# 2S_BATTERY_CHARGER_SCH.net
KiCad netlist of a schematic drawn in Altium Designer
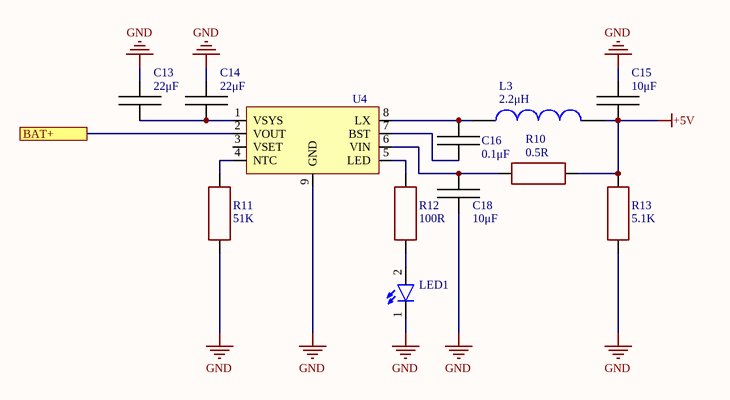
[diagram p0: 2S_BATTERY_CHARGER_SCH.SchDoc]

(export (version "E")
  (design (tool "Eeschema 10.0.6"))
  (components
    (comp (ref "C13")
      (value "22μF")
      (footprint "CAP: 0603")
      (fields (field (name "VOLTAGE") "??V") (field (name "Comment") "Cap_0603"))
      (libsource (lib "capacitor") (part "Cap_0603"))
    )
    (comp (ref "C14")
      (value "22μF")
      (footprint "CAP: 0603")
      (fields (field (name "VOLTAGE") "??V") (field (name "Comment") "Cap_0603"))
      (libsource (lib "capacitor") (part "Cap_0603"))
    )
    (comp (ref "C15")
      (value "10μF")
      (footprint "CAP: 0603")
      (fields (field (name "VOLTAGE") "??V") (field (name "Comment") "Cap_0603"))
      (libsource (lib "capacitor") (part "Cap_0603"))
    )
    (comp (ref "C16")
      (value "0.1μF")
      (footprint "CAP: 0603")
      (fields (field (name "VOLTAGE") "??V") (field (name "Comment") "Cap_0603"))
      (libsource (lib "capacitor") (part "Cap_0603"))
    )
    (comp (ref "C18")
      (value "10μF")
      (footprint "CAP: 0603")
      (fields (field (name "VOLTAGE") "??V") (field (name "Comment") "Cap_0603"))
      (libsource (lib "capacitor") (part "Cap_0603"))
    )
    (comp (ref "L3")
      (value "2.2μH")
      (footprint "CD43")
      (description "SMD Power Inductor")
      (fields (field (name "MANUFACTURER") "SUMIDA") (field (name "Comment") "CD43"))
      (libsource (lib "MY_INT_LIB") (part "CD43"))
    )
    (comp (ref "LED1")
      (value "LED_0603")
      (footprint "LED_0603")
      (libsource (lib "MY_INT_LIB") (part "LED_0603"))
    )
    (comp (ref "R10")
      (value "0.5R")
      (footprint "RES: 0603")
      (fields (field (name "TOLERANCE") "±5%") (field (name "Comment") "Resistor_0603"))
      (libsource (lib "") (part "Resistor_0603_1"))
    )
    (comp (ref "R11")
      (value "51K")
      (footprint "RES: 0603")
      (fields (field (name "TOLERANCE") "±5%") (field (name "Comment") "Resistor_0603"))
      (libsource (lib "resistor") (part "Resistor_0603"))
    )
    (comp (ref "R12")
      (value "100R")
      (footprint "RES: 0603")
      (fields (field (name "TOLERANCE") "±5%") (field (name "Comment") "Resistor_0603"))
      (libsource (lib "resistor") (part "Resistor_0603"))
    )
    (comp (ref "R13")
      (value "5.1K")
      (footprint "RES: 0603")
      (fields (field (name "TOLERANCE") "±5%") (field (name "Comment") "Resistor_0603"))
      (libsource (lib "resistor") (part "Resistor_0603"))
    )
    (comp (ref "U4")
      (value "IP2325")
      (footprint "ESOP-8")
      (description "2s charge Module")
      (fields (field (name "MANUFACTURER") "INJOINIC"))
      (libsource (lib "MY_INT_LIB") (part "IP2325"))
    )
  )
  (nets
    (net (code "1") (name "+5V") (class "Default")
      (node (ref "C15") (pin "2") (pinfunction "2_2") (pintype "passive"))
      (node (ref "L3") (pin "1") (pinfunction "1_1") (pintype "passive"))
      (node (ref "R10") (pin "1") (pinfunction "1_1") (pintype "passive"))
      (node (ref "R13") (pin "2") (pinfunction "2_2") (pintype "passive"))
    )
    (net (code "2") (name "/BAT+") (class "Default")
      (node (ref "U4") (pin "2") (pinfunction "VOUT_2") (pintype "passive"))
    )
    (net (code "3") (name "GND") (class "Default")
      (node (ref "C13") (pin "1") (pinfunction "1_1") (pintype "passive"))
      (node (ref "C14") (pin "1") (pinfunction "1_1") (pintype "passive"))
      (node (ref "C15") (pin "1") (pinfunction "1_1") (pintype "passive"))
      (node (ref "C18") (pin "1") (pinfunction "1_1") (pintype "passive"))
      (node (ref "LED1") (pin "1") (pintype "passive"))
      (node (ref "R11") (pin "1") (pinfunction "1_1") (pintype "passive"))
      (node (ref "R13") (pin "1") (pinfunction "1_1") (pintype "passive"))
      (node (ref "U4") (pin "9") (pinfunction "GND_9") (pintype "passive"))
    )
    (net (code "4") (name "Net-(LED1-Pad2)") (class "Default")
      (node (ref "LED1") (pin "2") (pintype "passive"))
      (node (ref "R12") (pin "1") (pinfunction "1_1") (pintype "passive"))
    )
    (net (code "5") (name "Net-(U4-BST)") (class "Default")
      (node (ref "C16") (pin "1") (pinfunction "1_1") (pintype "passive"))
      (node (ref "U4") (pin "7") (pinfunction "BST_7") (pintype "passive"))
    )
    (net (code "6") (name "Net-(U4-LED)") (class "Default")
      (node (ref "R12") (pin "2") (pinfunction "2_2") (pintype "passive"))
      (node (ref "U4") (pin "5") (pinfunction "LED_5") (pintype "passive"))
    )
    (net (code "7") (name "Net-(U4-LX)") (class "Default")
      (node (ref "C16") (pin "2") (pinfunction "2_2") (pintype "passive"))
      (node (ref "L3") (pin "2") (pinfunction "2_2") (pintype "passive"))
      (node (ref "U4") (pin "8") (pinfunction "LX_8") (pintype "passive"))
    )
    (net (code "8") (name "Net-(U4-NTC)") (class "Default")
      (node (ref "R11") (pin "2") (pinfunction "2_2") (pintype "passive"))
      (node (ref "U4") (pin "4") (pinfunction "NTC_4") (pintype "passive"))
    )
    (net (code "9") (name "Net-(U4-VIN)") (class "Default")
      (node (ref "C18") (pin "2") (pinfunction "2_2") (pintype "passive"))
      (node (ref "R10") (pin "2") (pinfunction "2_2") (pintype "passive"))
      (node (ref "U4") (pin "6") (pinfunction "VIN_6") (pintype "passive"))
    )
    (net (code "10") (name "Net-(U4-VSYS)") (class "Default")
      (node (ref "C13") (pin "2") (pinfunction "2_2") (pintype "passive"))
      (node (ref "C14") (pin "2") (pinfunction "2_2") (pintype "passive"))
      (node (ref "U4") (pin "1") (pinfunction "VSYS_1") (pintype "passive"))
    )
    (net (code "11") (name "unconnected-(U4-VSET-Pad3)") (class "Default")
      (node (ref "U4") (pin "3") (pinfunction "VSET_3") (pintype "passive"))
    )
  )
)
